# Power_Supply_AMP.net
KiCad netlist of a schematic drawn in Altium Designer
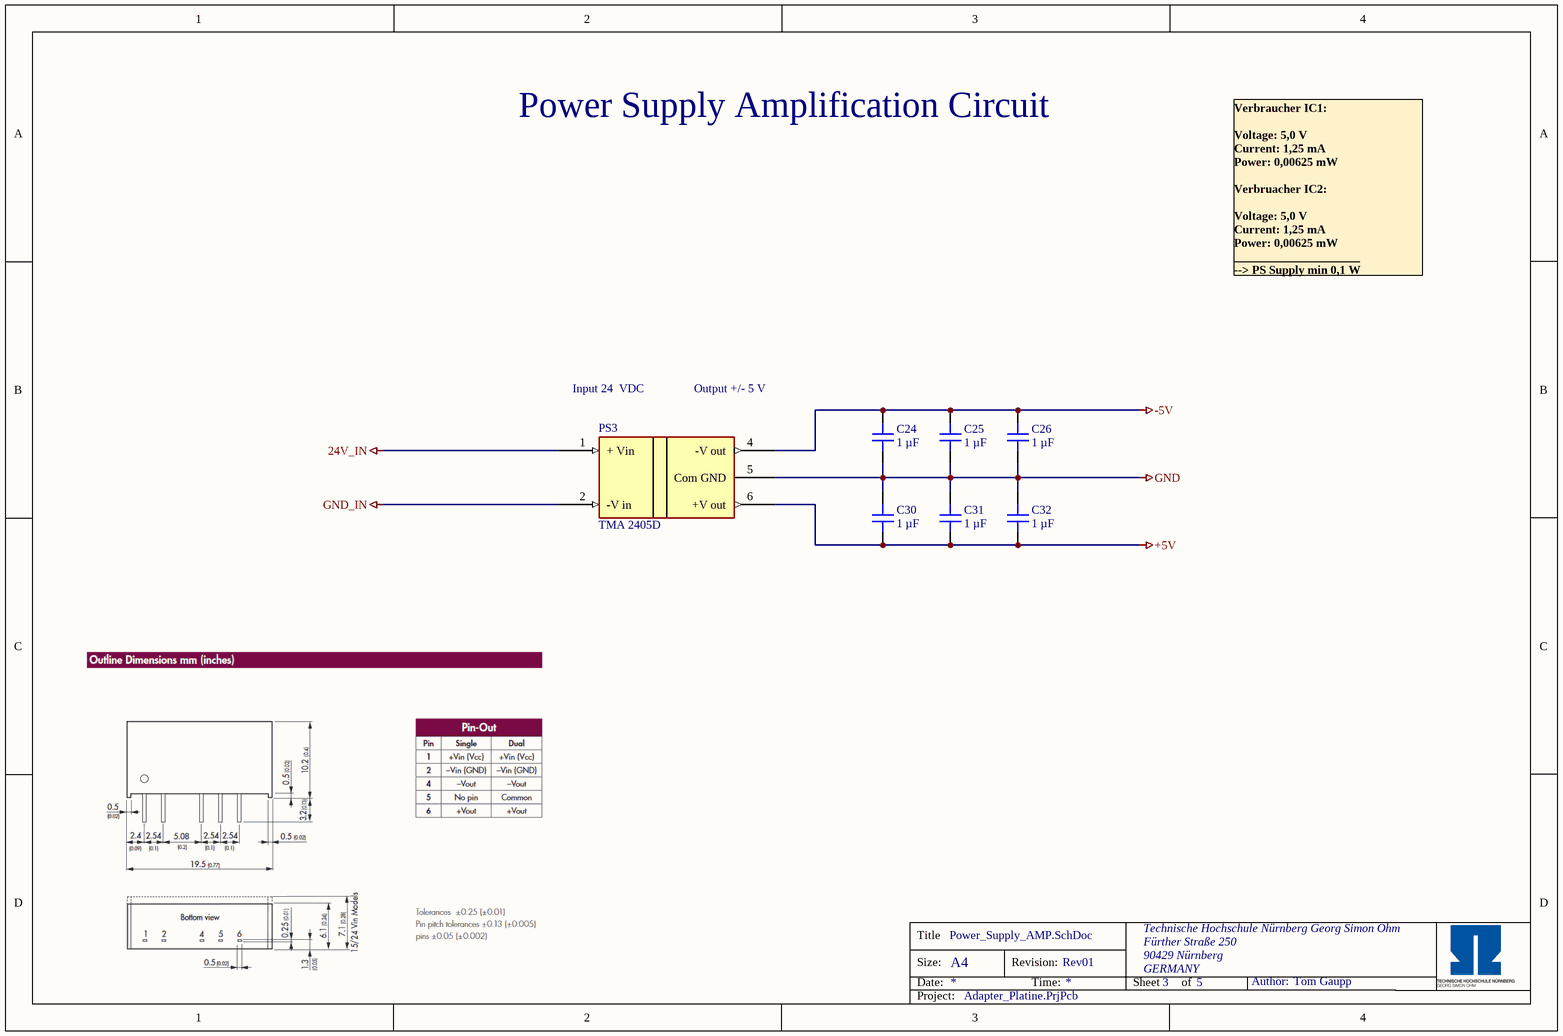
[diagram p0: Power_Supply_AMP.SchDoc]

(export (version "E")
  (design (tool "Eeschema 10.0.6"))
  (components
    (comp (ref "C24")
      (value "1 µF")
      (footprint "C_0603")
      (description "50V 1uF X5R ±10% 0603  Multilayer Ceramic Capacitors MLCC - SMD/SMT ROHS")
      (fields
        (field (name "MANUFACTURER") "Samsung Electro-Mechanics")
        (field (name "MANUFACTURER PART NUMBER") "CL10A105KB8NNNC")
        (field (name "CREATED FROM") "MGremer")
      )
      (libsource (lib "user") (part "Capacitor"))
    )
    (comp (ref "C25")
      (value "1 µF")
      (footprint "C_0603")
      (description "50V 1uF X5R ±10% 0603  Multilayer Ceramic Capacitors MLCC - SMD/SMT ROHS")
      (fields
        (field (name "MANUFACTURER") "Samsung Electro-Mechanics")
        (field (name "MANUFACTURER PART NUMBER") "CL10A105KB8NNNC")
        (field (name "CREATED FROM") "MGremer")
      )
      (libsource (lib "user") (part "Capacitor"))
    )
    (comp (ref "C26")
      (value "1 µF")
      (footprint "C_0603")
      (description "50V 1uF X5R ±10% 0603  Multilayer Ceramic Capacitors MLCC - SMD/SMT ROHS")
      (fields
        (field (name "MANUFACTURER") "Samsung Electro-Mechanics")
        (field (name "MANUFACTURER PART NUMBER") "CL10A105KB8NNNC")
        (field (name "CREATED FROM") "MGremer")
      )
      (libsource (lib "user") (part "Capacitor"))
    )
    (comp (ref "C30")
      (value "1 µF")
      (footprint "C_0603")
      (description "50V 1uF X5R ±10% 0603  Multilayer Ceramic Capacitors MLCC - SMD/SMT ROHS")
      (fields
        (field (name "MANUFACTURER") "Samsung Electro-Mechanics")
        (field (name "MANUFACTURER PART NUMBER") "CL10A105KB8NNNC")
        (field (name "CREATED FROM") "MGremer")
      )
      (libsource (lib "user") (part "Capacitor"))
    )
    (comp (ref "C31")
      (value "1 µF")
      (footprint "C_0603")
      (description "50V 1uF X5R ±10% 0603  Multilayer Ceramic Capacitors MLCC - SMD/SMT ROHS")
      (fields
        (field (name "MANUFACTURER") "Samsung Electro-Mechanics")
        (field (name "MANUFACTURER PART NUMBER") "CL10A105KB8NNNC")
        (field (name "CREATED FROM") "MGremer")
      )
      (libsource (lib "user") (part "Capacitor"))
    )
    (comp (ref "C32")
      (value "1 µF")
      (footprint "C_0603")
      (description "50V 1uF X5R ±10% 0603  Multilayer Ceramic Capacitors MLCC - SMD/SMT ROHS")
      (fields
        (field (name "MANUFACTURER") "Samsung Electro-Mechanics")
        (field (name "MANUFACTURER PART NUMBER") "CL10A105KB8NNNC")
        (field (name "CREATED FROM") "MGremer")
      )
      (libsource (lib "user") (part "Capacitor"))
    )
    (comp (ref "PS3")
      (value "TMA 2405D")
      (footprint "eigene_lib_alt:TMA 2405D")
      (libsource (lib "eigene_lib_alt") (part "TMA 2405D"))
    )
  )
  (nets
    (net (code "1") (name "+5V") (class "Default")
      (node (ref "C30") (pin "1") (pinfunction "1_1") (pintype "passive"))
      (node (ref "C31") (pin "1") (pinfunction "1_1") (pintype "passive"))
      (node (ref "C32") (pin "1") (pinfunction "1_1") (pintype "passive"))
      (node (ref "PS3") (pin "6") (pinfunction "+V_out_6") (pintype "output"))
    )
    (net (code "2") (name "-5V") (class "Default")
      (node (ref "C24") (pin "2") (pinfunction "2_2") (pintype "passive"))
      (node (ref "C25") (pin "2") (pinfunction "2_2") (pintype "passive"))
      (node (ref "C26") (pin "2") (pinfunction "2_2") (pintype "passive"))
      (node (ref "PS3") (pin "4") (pinfunction "-V_out_4") (pintype "output"))
    )
    (net (code "3") (name "24V_IN") (class "Default")
      (node (ref "PS3") (pin "1") (pinfunction "+_Vin_1") (pintype "input"))
    )
    (net (code "4") (name "GND") (class "Default")
      (node (ref "C24") (pin "1") (pinfunction "1_1") (pintype "passive"))
      (node (ref "C25") (pin "1") (pinfunction "1_1") (pintype "passive"))
      (node (ref "C26") (pin "1") (pinfunction "1_1") (pintype "passive"))
      (node (ref "C30") (pin "2") (pinfunction "2_2") (pintype "passive"))
      (node (ref "C31") (pin "2") (pinfunction "2_2") (pintype "passive"))
      (node (ref "C32") (pin "2") (pinfunction "2_2") (pintype "passive"))
      (node (ref "PS3") (pin "5") (pinfunction "Com_GND_5") (pintype "passive"))
    )
    (net (code "5") (name "GND_IN") (class "Default")
      (node (ref "PS3") (pin "2") (pinfunction "-V_in_2") (pintype "input"))
    )
  )
)
